# Mainboard_ThermistorAmp.net
KiCad netlist of a schematic drawn in Altium Designer
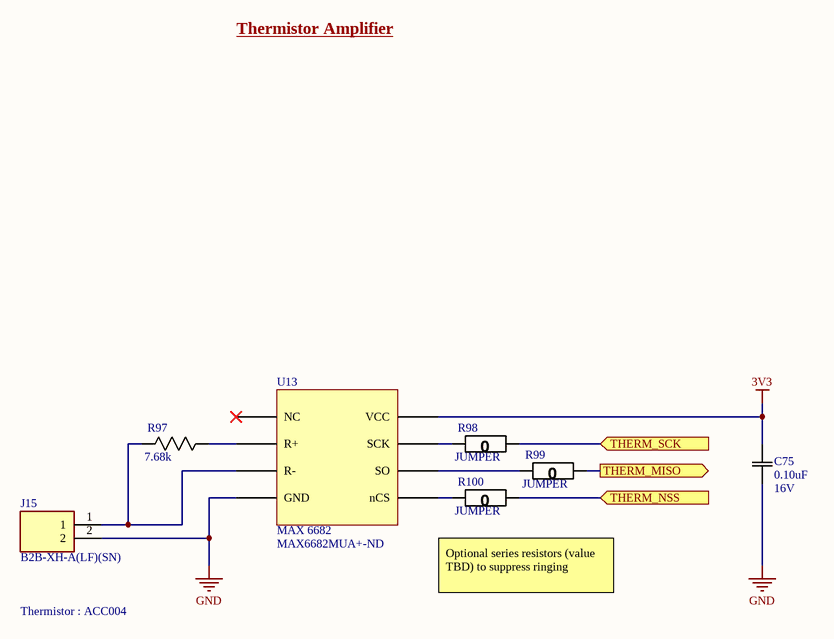
[diagram p0: Mainboard_ThermistorAmp.SchDoc]

(export (version "E")
  (design (tool "Eeschema 10.0.6"))
  (components
    (comp (ref "C75")
      (value "0.10uF")
      (footprint "0805")
      (description "CAP CER 0.10UF 16V X5R 0603/0805")
      (fields (field (name "TOLERANCE") "10%") (field (name "RATING") "16V"))
      (libsource (lib "AltiumLibraries") (part "CAP 0.10uF 16V"))
    )
    (comp (ref "J15")
      (value "B2B-XH-A(LF)(SN)")
      (footprint "JST_B2B-XH-A(LF)(SN)")
      (description "Connector Header Through Hole 2 position 0.098 _2.50mm_\r\nJST XH")
      (fields (field (name "MP") "B2B-XH-A_LF__SN_") (field (name "MF") "JST Sales"))
      (libsource (lib "AltiumLibraries") (part "B2B-XH-A(LF)(SN)"))
    )
    (comp (ref "R97")
      (value "7.68k")
      (footprint "0805")
      (description "RES SMD 7.68K OHM 0.1% 0.15W 0805")
      (fields (field (name "TOLERANCE") "5%"))
      (libsource (lib "AltiumLibraries") (part "RES 7.68k 0.15W"))
    )
    (comp (ref "R98")
      (value "JUMPER")
      (footprint "0805")
      (description "RES SMD 0 OHM JUMPER GENERIC 0805")
      (libsource (lib "AltiumLibraries") (part "RES 0 JUMPER"))
    )
    (comp (ref "R99")
      (value "JUMPER")
      (footprint "0805")
      (description "RES SMD 0 OHM JUMPER GENERIC 0805")
      (libsource (lib "AltiumLibraries") (part "RES 0 JUMPER"))
    )
    (comp (ref "R100")
      (value "JUMPER")
      (footprint "0805")
      (description "RES SMD 0 OHM JUMPER GENERIC 0805")
      (libsource (lib "AltiumLibraries") (part "RES 0 JUMPER"))
    )
    (comp (ref "U13")
      (value "MAX 6682")
      (footprint "8-MSOP")
      (description "MAX 6685 Thermistor - SPI converter, 8bit")
      (fields (field (name "SUPPLIER PART NUMBER 1") "MAX6682MUA+-ND"))
      (libsource (lib "AltiumLibraries") (part "MAX 6682"))
    )
  )
  (nets
    (net (code "1") (name "/THERM_MISO") (class "Default")
      (node (ref "R99") (pin "1") (pinfunction "R1_1") (pintype "passive"))
    )
    (net (code "2") (name "/THERM_NSS") (class "Default")
      (node (ref "R100") (pin "1") (pinfunction "R1_1") (pintype "passive"))
    )
    (net (code "3") (name "/THERM_SCK") (class "Default")
      (node (ref "R98") (pin "1") (pinfunction "R1_1") (pintype "passive"))
    )
    (net (code "4") (name "3V3") (class "Default")
      (node (ref "C75") (pin "1") (pinfunction "C1_1") (pintype "passive"))
      (node (ref "U13") (pin "8") (pinfunction "VCC_8") (pintype "passive"))
    )
    (net (code "5") (name "GND") (class "Default")
      (node (ref "C75") (pin "2") (pinfunction "C2_2") (pintype "passive"))
      (node (ref "J15") (pin "2") (pinfunction "2_2") (pintype "passive"))
      (node (ref "U13") (pin "4") (pinfunction "GND_4") (pintype "passive"))
    )
    (net (code "6") (name "Net-(R97-R1)") (class "Default")
      (node (ref "R97") (pin "1") (pinfunction "R1_1") (pintype "passive"))
      (node (ref "U13") (pin "2") (pinfunction "R+_2") (pintype "passive"))
    )
    (net (code "7") (name "Net-(R97-R2)") (class "Default")
      (node (ref "J15") (pin "1") (pinfunction "1_1") (pintype "passive"))
      (node (ref "R97") (pin "2") (pinfunction "R2_2") (pintype "passive"))
      (node (ref "U13") (pin "3") (pinfunction "R-_3") (pintype "passive"))
    )
    (net (code "8") (name "Net-(R98-R2)") (class "Default")
      (node (ref "R98") (pin "2") (pinfunction "R2_2") (pintype "passive"))
      (node (ref "U13") (pin "7") (pinfunction "SCK_7") (pintype "passive"))
    )
    (net (code "9") (name "Net-(R99-R2)") (class "Default")
      (node (ref "R99") (pin "2") (pinfunction "R2_2") (pintype "passive"))
      (node (ref "U13") (pin "6") (pinfunction "SO_6") (pintype "passive"))
    )
    (net (code "10") (name "Net-(R100-R2)") (class "Default")
      (node (ref "R100") (pin "2") (pinfunction "R2_2") (pintype "passive"))
      (node (ref "U13") (pin "5") (pinfunction "nCS_5") (pintype "passive"))
    )
    (net (code "11") (name "unconnected-(U13-NC-Pad1)") (class "Default")
      (node (ref "U13") (pin "1") (pinfunction "NC_1") (pintype "passive+no_connect"))
    )
  )
)
